# SparkFun_Dev_ESP32_C3_MINI.net
KiCad netlist of a schematic drawn in EAGLE
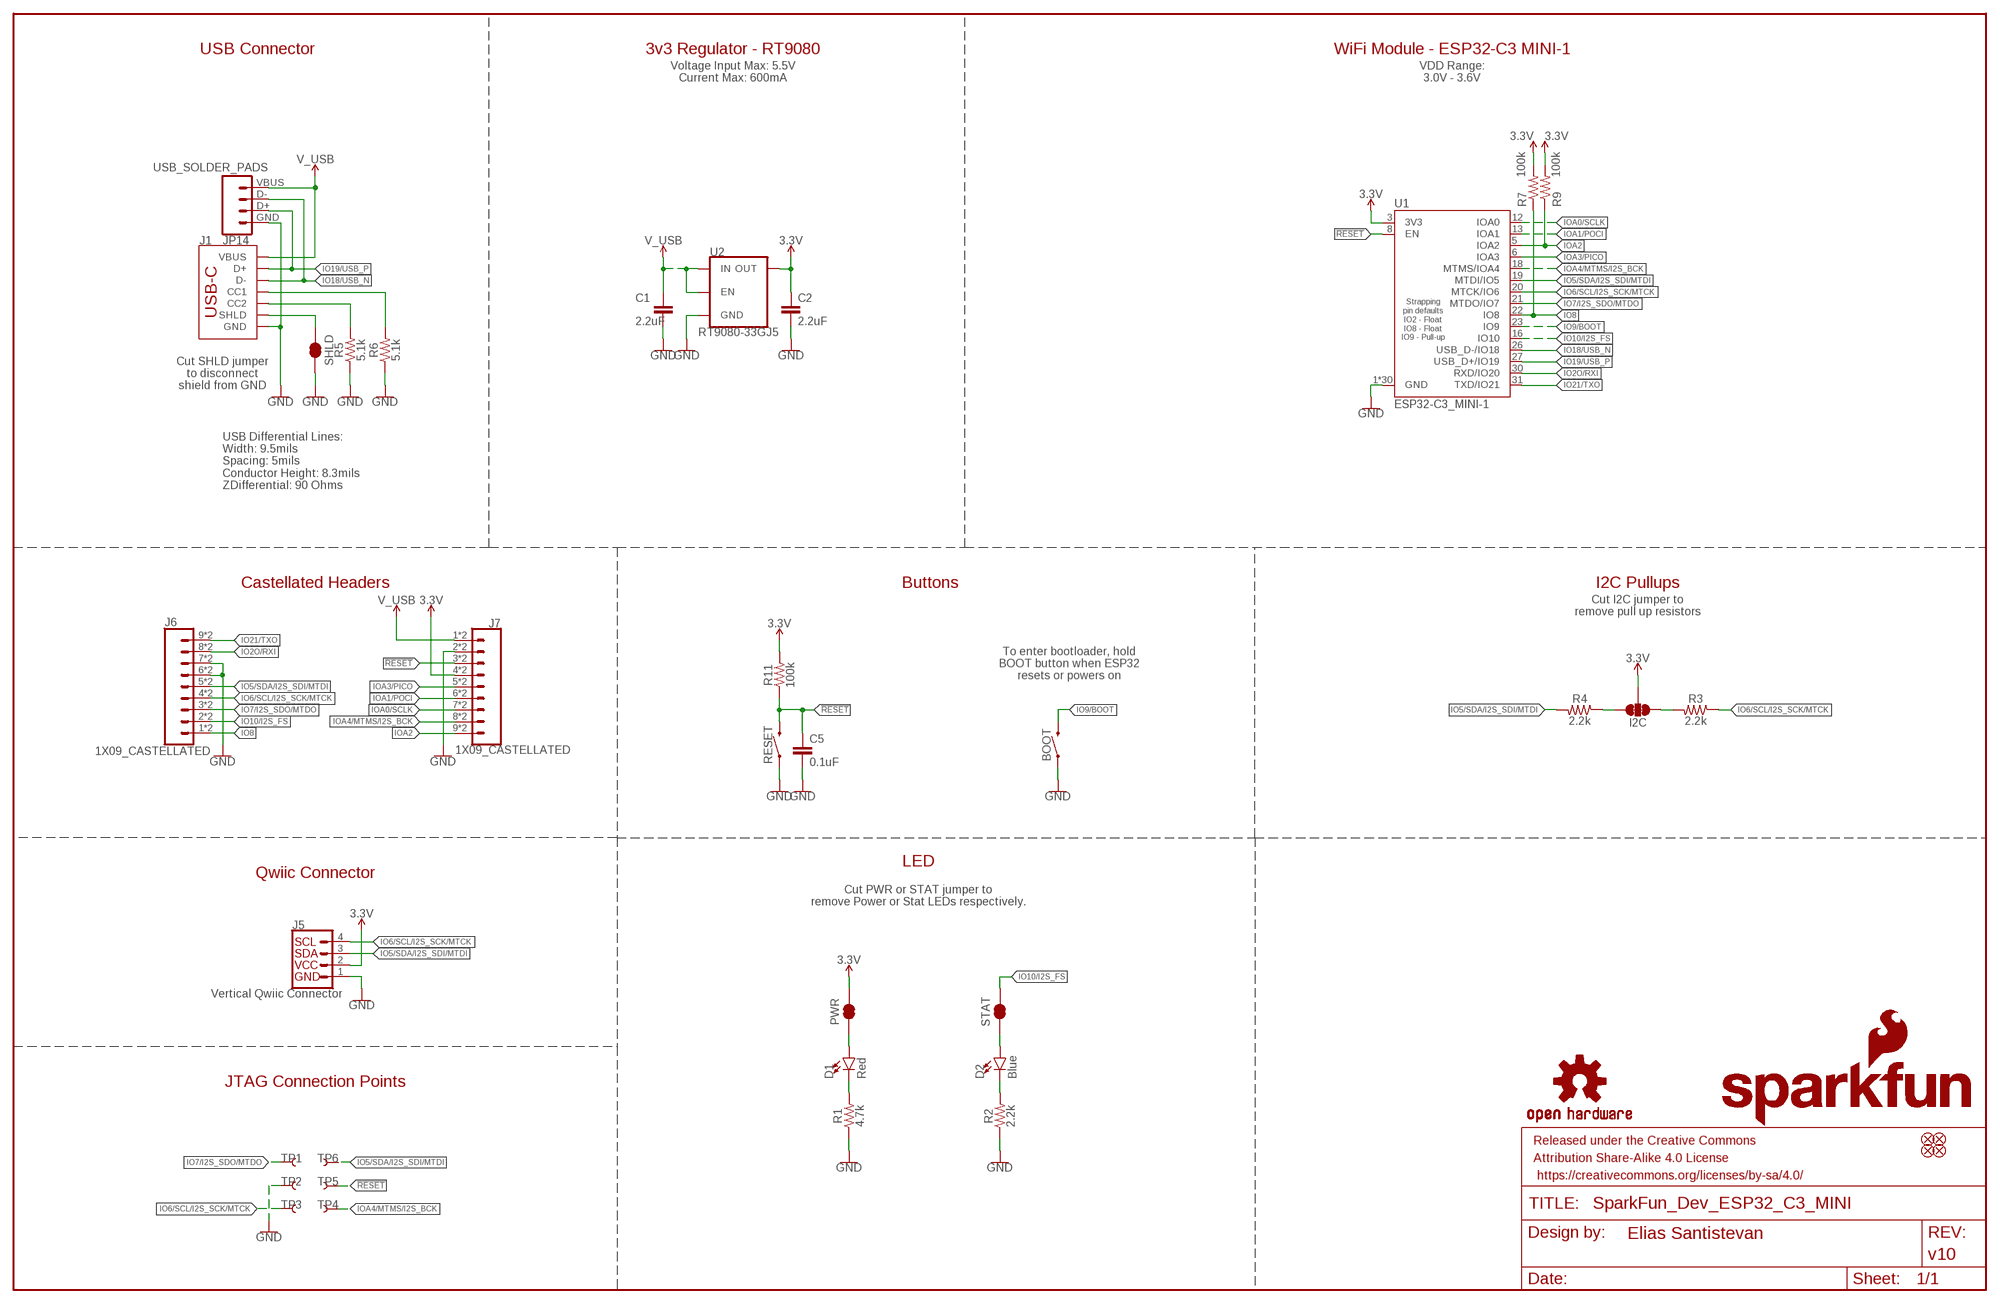
[diagram p0: schematic, sheet 1]

(export (version "E")
  (design (tool "Eeschema 10.0.6"))
  (components
    (comp (ref "BOOT")
      (value "MOMENTARY-SWITCH-SPST-SMD-4.6X2.8MM")
      (footprint "eagle-import:TACTILE_SWITCH_SMD_4.6X2.8MM")
      (libsource (lib "eagle-import") (part "MOMENTARY-SWITCH-SPST-SMD-4.6X2.8MM"))
    )
    (comp (ref "C1")
      (value "2.2uF")
      (footprint "eagle-import:0402-TIGHT")
      (libsource (lib "eagle-import") (part "2.2UF-0402_TIGHT-10V-10%-X5R"))
    )
    (comp (ref "C2")
      (value "2.2uF")
      (footprint "eagle-import:0402-TIGHT")
      (libsource (lib "eagle-import") (part "2.2UF-0402_TIGHT-10V-10%-X5R"))
    )
    (comp (ref "C5")
      (value "0.1uF")
      (footprint "eagle-import:0402-TIGHT")
      (libsource (lib "eagle-import") (part "0.1UF-0402T-6.3V-10%-X7R"))
    )
    (comp (ref "D1")
      (value "Red")
      (footprint "eagle-import:LED-0603")
      (libsource (lib "eagle-import") (part "LED-RED_0603-KB"))
    )
    (comp (ref "D2")
      (value "Blue")
      (footprint "eagle-import:LED-0603")
      (libsource (lib "eagle-import") (part "LED-BLUE0603"))
    )
    (comp (ref "FD1")
      (value "FIDUCIALUFIDUCIAL")
      (footprint "eagle-import:FIDUCIAL-MICRO")
      (libsource (lib "eagle-import") (part "FIDUCIALUFIDUCIAL"))
    )
    (comp (ref "FD2")
      (value "FIDUCIALUFIDUCIAL")
      (footprint "eagle-import:FIDUCIAL-MICRO")
      (libsource (lib "eagle-import") (part "FIDUCIALUFIDUCIAL"))
    )
    (comp (ref "FD3")
      (value "FIDUCIALUFIDUCIAL")
      (footprint "eagle-import:FIDUCIAL-MICRO")
      (libsource (lib "eagle-import") (part "FIDUCIALUFIDUCIAL"))
    )
    (comp (ref "FD4")
      (value "FIDUCIALUFIDUCIAL")
      (footprint "eagle-import:FIDUCIAL-MICRO")
      (libsource (lib "eagle-import") (part "FIDUCIALUFIDUCIAL"))
    )
    (comp (ref "FRAME2")
      (value "FRAME-LEDGER")
      (footprint "eagle-import:CREATIVE_COMMONS")
      (fields (field (name "DESIGNER") "Elias Santistevan") (field (name "REV") "v10"))
      (libsource (lib "eagle-import") (part "FRAME-LEDGER"))
    )
    (comp (ref "I2C")
      (value "JUMPER-SMT_3_2-NC_TRACE_SILK")
      (footprint "eagle-import:SMT-JUMPER_3_2-NC_TRACE_SILK")
      (libsource (lib "eagle-import") (part "JUMPER-SMT_3_2-NC_TRACE_SILK"))
    )
    (comp (ref "J1")
      (value "USB Female Type C Connector")
      (footprint "eagle-import:USB-C-16P_4LAYER-PADS")
      (libsource (lib "eagle-import") (part "USB_C_4-LAYER_PADS"))
    )
    (comp (ref "J5")
      (value "Vertical Qwiic Connector")
      (footprint "eagle-import:JST04_1MM_VERT")
      (libsource (lib "eagle-import") (part "QWIIC_CONNECTOR"))
    )
    (comp (ref "J6")
      (value "1X09_CASTELLATED")
      (footprint "eagle-import:1X09_CASTELLATED")
      (libsource (lib "eagle-import") (part "1X09_CASTELLATED"))
    )
    (comp (ref "J7")
      (value "1X09_CASTELLATED")
      (footprint "eagle-import:1X09_CASTELLATED")
      (libsource (lib "eagle-import") (part "1X09_CASTELLATED"))
    )
    (comp (ref "JP14")
      (value "USB_SOLDER_PADS")
      (footprint "eagle-import:USB-SOLDER-PADS")
      (libsource (lib "eagle-import") (part "USB_SOLDER_PADS"))
    )
    (comp (ref "LOGO1")
      (value "SFE_LOGO_NAME_FLAMEBLANK")
      (footprint "eagle-import:BLANK")
      (libsource (lib "eagle-import") (part "SFE_LOGO_NAME_FLAMEBLANK"))
    )
    (comp (ref "LOGO3")
      (value "OSHW-LOGOS")
      (footprint "eagle-import:OSHW-LOGO-S")
      (libsource (lib "eagle-import") (part "OSHW-LOGOS"))
    )
    (comp (ref "PWR")
      (value "JUMPER-SMT_2_NC_TRACE_SILK")
      (footprint "eagle-import:SMT-JUMPER_2_NC_TRACE_SILK")
      (libsource (lib "eagle-import") (part "JUMPER-SMT_2_NC_TRACE_SILK"))
    )
    (comp (ref "R1")
      (value "4.7k")
      (footprint "eagle-import:0402-TIGHT")
      (libsource (lib "eagle-import") (part "4.7KOHM-0402T-1/16W-1%"))
    )
    (comp (ref "R2")
      (value "2.2k")
      (footprint "eagle-import:0402-TIGHT")
      (libsource (lib "eagle-import") (part "2.2KOHM-0402T-1/16W-1%"))
    )
    (comp (ref "R3")
      (value "2.2k")
      (footprint "eagle-import:0402-TIGHT")
      (libsource (lib "eagle-import") (part "2.2KOHM-0402T-1/16W-1%"))
    )
    (comp (ref "R4")
      (value "2.2k")
      (footprint "eagle-import:0402-TIGHT")
      (libsource (lib "eagle-import") (part "2.2KOHM-0402T-1/16W-1%"))
    )
    (comp (ref "R5")
      (value "5.1k")
      (footprint "eagle-import:0402-TIGHT")
      (libsource (lib "eagle-import") (part "5.1KOHM-0402T-1/16W-1%"))
    )
    (comp (ref "R6")
      (value "5.1k")
      (footprint "eagle-import:0402-TIGHT")
      (libsource (lib "eagle-import") (part "5.1KOHM-0402T-1/16W-1%"))
    )
    (comp (ref "R7")
      (value "100k")
      (footprint "eagle-import:0402-TIGHT")
      (libsource (lib "eagle-import") (part "100KOHM-0402T-1/16W-1%"))
    )
    (comp (ref "R9")
      (value "100k")
      (footprint "eagle-import:0402-TIGHT")
      (libsource (lib "eagle-import") (part "100KOHM-0402T-1/16W-1%"))
    )
    (comp (ref "R11")
      (value "100k")
      (footprint "eagle-import:0402-TIGHT")
      (libsource (lib "eagle-import") (part "100KOHM-0402T-1/16W-1%"))
    )
    (comp (ref "RESET")
      (value "MOMENTARY-SWITCH-SPST-SMD-4.6X2.8MM")
      (footprint "eagle-import:TACTILE_SWITCH_SMD_4.6X2.8MM")
      (libsource (lib "eagle-import") (part "MOMENTARY-SWITCH-SPST-SMD-4.6X2.8MM"))
    )
    (comp (ref "SHLD")
      (value "JUMPER-SMT_2_NC_TRACE_SILK")
      (footprint "eagle-import:SMT-JUMPER_2_NC_TRACE_SILK")
      (libsource (lib "eagle-import") (part "JUMPER-SMT_2_NC_TRACE_SILK"))
    )
    (comp (ref "STAT")
      (value "JUMPER-SMT_2_NC_TRACE_SILK")
      (footprint "eagle-import:SMT-JUMPER_2_NC_TRACE_SILK")
      (libsource (lib "eagle-import") (part "JUMPER-SMT_2_NC_TRACE_SILK"))
    )
    (comp (ref "TP1")
      (value "TEST-POINT3X5")
      (footprint "eagle-import:PAD.03X.05")
      (libsource (lib "eagle-import") (part "TEST-POINT3X5"))
    )
    (comp (ref "TP2")
      (value "TEST-POINT3X5")
      (footprint "eagle-import:PAD.03X.05")
      (libsource (lib "eagle-import") (part "TEST-POINT3X5"))
    )
    (comp (ref "TP3")
      (value "TEST-POINT3X5")
      (footprint "eagle-import:PAD.03X.05")
      (libsource (lib "eagle-import") (part "TEST-POINT3X5"))
    )
    (comp (ref "TP4")
      (value "TEST-POINT3X5")
      (footprint "eagle-import:PAD.03X.05")
      (libsource (lib "eagle-import") (part "TEST-POINT3X5"))
    )
    (comp (ref "TP5")
      (value "TEST-POINT3X5")
      (footprint "eagle-import:PAD.03X.05")
      (libsource (lib "eagle-import") (part "TEST-POINT3X5"))
    )
    (comp (ref "TP6")
      (value "TEST-POINT3X5")
      (footprint "eagle-import:PAD.03X.05")
      (libsource (lib "eagle-import") (part "TEST-POINT3X5"))
    )
    (comp (ref "U1")
      (value "ESP32-C3_MINI-1")
      (footprint "eagle-import:ESP32-C3-MINI-1")
      (libsource (lib "eagle-import") (part "ESP32-C3_MINI-1"))
    )
    (comp (ref "U2")
      (value "RT9080-33GJ5")
      (footprint "eagle-import:SOT23-5")
      (libsource (lib "eagle-import") (part "V_REG_RT9080"))
    )
  )
  (nets
    (net (code "1") (name "/~{RESET}") (class "Default")
      (node (ref "C5") (pin "1") (pinfunction "1_1") (pintype "passive"))
      (node (ref "J7") (pin "3") (pinfunction "3_3") (pintype "passive"))
      (node (ref "J7") (pin "3B") (pinfunction "3_3B") (pintype "passive"))
      (node (ref "R11") (pin "1") (pinfunction "1_1") (pintype "passive"))
      (node (ref "RESET") (pin "3") (pinfunction "2_3") (pintype "passive"))
      (node (ref "RESET") (pin "4") (pinfunction "2_4") (pintype "passive"))
      (node (ref "TP5") (pin "1") (pinfunction "1_1") (pintype "bidirectional"))
      (node (ref "U1") (pin "8") (pinfunction "EN_8") (pintype "bidirectional"))
    )
    (net (code "2") (name "3.3V") (class "Default")
      (node (ref "C2") (pin "1") (pinfunction "1_1") (pintype "passive"))
      (node (ref "I2C") (pin "2") (pinfunction "2_2") (pintype "passive"))
      (node (ref "J5") (pin "2") (pinfunction "2_2") (pintype "power_in"))
      (node (ref "J7") (pin "4") (pinfunction "4_4") (pintype "passive"))
      (node (ref "J7") (pin "4B") (pinfunction "4_4B") (pintype "passive"))
      (node (ref "PWR") (pin "2") (pinfunction "2_2") (pintype "passive"))
      (node (ref "R11") (pin "2") (pinfunction "2_2") (pintype "passive"))
      (node (ref "R7") (pin "2") (pinfunction "2_2") (pintype "passive"))
      (node (ref "R9") (pin "2") (pinfunction "2_2") (pintype "passive"))
      (node (ref "U1") (pin "3") (pinfunction "3V3_3") (pintype "bidirectional"))
      (node (ref "U2") (pin "5") (pinfunction "OUT_5") (pintype "passive"))
    )
    (net (code "3") (name "GND") (class "Default")
      (node (ref "BOOT") (pin "1") (pinfunction "1_1") (pintype "passive"))
      (node (ref "BOOT") (pin "2") (pinfunction "1_2") (pintype "passive"))
      (node (ref "C1") (pin "2") (pinfunction "2_2") (pintype "passive"))
      (node (ref "C2") (pin "2") (pinfunction "2_2") (pintype "passive"))
      (node (ref "C5") (pin "2") (pinfunction "2_2") (pintype "passive"))
      (node (ref "J1") (pin "GND") (pinfunction "GND_GND") (pintype "bidirectional"))
      (node (ref "J1") (pin "GND2") (pinfunction "GND_GND2") (pintype "bidirectional"))
      (node (ref "J5") (pin "1") (pinfunction "1_1") (pintype "power_in"))
      (node (ref "J6") (pin "6") (pinfunction "6_6") (pintype "passive"))
      (node (ref "J6") (pin "6B") (pinfunction "6_6B") (pintype "passive"))
      (node (ref "J6") (pin "7") (pinfunction "7_7") (pintype "passive"))
      (node (ref "J6") (pin "7B") (pinfunction "7_7B") (pintype "passive"))
      (node (ref "J7") (pin "2") (pinfunction "2_2") (pintype "passive"))
      (node (ref "J7") (pin "2B") (pinfunction "2_2B") (pintype "passive"))
      (node (ref "JP14") (pin "GND") (pinfunction "4_GND") (pintype "passive"))
      (node (ref "R1") (pin "1") (pinfunction "1_1") (pintype "passive"))
      (node (ref "R2") (pin "1") (pinfunction "1_1") (pintype "passive"))
      (node (ref "R5") (pin "1") (pinfunction "1_1") (pintype "passive"))
      (node (ref "R6") (pin "1") (pinfunction "1_1") (pintype "passive"))
      (node (ref "RESET") (pin "1") (pinfunction "1_1") (pintype "passive"))
      (node (ref "RESET") (pin "2") (pinfunction "1_2") (pintype "passive"))
      (node (ref "SHLD") (pin "2") (pinfunction "2_2") (pintype "passive"))
      (node (ref "TP2") (pin "1") (pinfunction "1_1") (pintype "bidirectional"))
      (node (ref "U1") (pin "1") (pinfunction "GND_1") (pintype "bidirectional"))
      (node (ref "U1") (pin "11") (pinfunction "GND_11") (pintype "bidirectional"))
      (node (ref "U1") (pin "14") (pinfunction "GND_14") (pintype "bidirectional"))
      (node (ref "U1") (pin "2") (pinfunction "GND_2") (pintype "bidirectional"))
      (node (ref "U1") (pin "36") (pinfunction "GND_36") (pintype "bidirectional"))
      (node (ref "U1") (pin "37") (pinfunction "GND_37") (pintype "bidirectional"))
      (node (ref "U1") (pin "38") (pinfunction "GND_38") (pintype "bidirectional"))
      (node (ref "U1") (pin "39") (pinfunction "GND_39") (pintype "bidirectional"))
      (node (ref "U1") (pin "40") (pinfunction "GND_40") (pintype "bidirectional"))
      (node (ref "U1") (pin "41") (pinfunction "GND_41") (pintype "bidirectional"))
      (node (ref "U1") (pin "42") (pinfunction "GND_42") (pintype "bidirectional"))
      (node (ref "U1") (pin "43") (pinfunction "GND_43") (pintype "bidirectional"))
      (node (ref "U1") (pin "44") (pinfunction "GND_44") (pintype "bidirectional"))
      (node (ref "U1") (pin "45") (pinfunction "GND_45") (pintype "bidirectional"))
      (node (ref "U1") (pin "46") (pinfunction "GND_46") (pintype "bidirectional"))
      (node (ref "U1") (pin "47") (pinfunction "GND_47") (pintype "bidirectional"))
      (node (ref "U1") (pin "48") (pinfunction "GND_48") (pintype "bidirectional"))
      (node (ref "U1") (pin "49.1") (pinfunction "GND_49.1") (pintype "bidirectional"))
      (node (ref "U1") (pin "49.2") (pinfunction "GND_49.2") (pintype "bidirectional"))
      (node (ref "U1") (pin "49.3") (pinfunction "GND_49.3") (pintype "bidirectional"))
      (node (ref "U1") (pin "49.4") (pinfunction "GND_49.4") (pintype "bidirectional"))
      (node (ref "U1") (pin "49.5") (pinfunction "GND_49.5") (pintype "bidirectional"))
      (node (ref "U1") (pin "49.6") (pinfunction "GND_49.6") (pintype "bidirectional"))
      (node (ref "U1") (pin "49.7") (pinfunction "GND_49.7") (pintype "bidirectional"))
      (node (ref "U1") (pin "49.8") (pinfunction "GND_49.8") (pintype "bidirectional"))
      (node (ref "U1") (pin "49.9") (pinfunction "GND_49.9") (pintype "bidirectional"))
      (node (ref "U1") (pin "50") (pinfunction "GND_50") (pintype "bidirectional"))
      (node (ref "U1") (pin "51") (pinfunction "GND_51") (pintype "bidirectional"))
      (node (ref "U1") (pin "52") (pinfunction "GND_52") (pintype "bidirectional"))
      (node (ref "U1") (pin "53") (pinfunction "GND_53") (pintype "bidirectional"))
      (node (ref "U2") (pin "2") (pinfunction "GND_2") (pintype "input"))
    )
    (net (code "4") (name "IO2O{slash}RXI") (class "Default")
      (node (ref "J6") (pin "8") (pinfunction "8_8") (pintype "passive"))
      (node (ref "J6") (pin "8B") (pinfunction "8_8B") (pintype "passive"))
      (node (ref "U1") (pin "30") (pinfunction "RXD/IO20_30") (pintype "bidirectional"))
    )
    (net (code "5") (name "IO5{slash}SDA{slash}I2S_SDI{slash}MTDI") (class "Default")
      (node (ref "J5") (pin "3") (pinfunction "3_3") (pintype "passive"))
      (node (ref "J6") (pin "5") (pinfunction "5_5") (pintype "passive"))
      (node (ref "J6") (pin "5B") (pinfunction "5_5B") (pintype "passive"))
      (node (ref "R4") (pin "2") (pinfunction "2_2") (pintype "passive"))
      (node (ref "TP6") (pin "1") (pinfunction "1_1") (pintype "bidirectional"))
      (node (ref "U1") (pin "19") (pinfunction "MTDI/IO5_19") (pintype "bidirectional"))
    )
    (net (code "6") (name "IO6{slash}SCL{slash}I2S_SCK{slash}MTCK") (class "Default")
      (node (ref "J5") (pin "4") (pinfunction "4_4") (pintype "passive"))
      (node (ref "J6") (pin "4") (pinfunction "4_4") (pintype "passive"))
      (node (ref "J6") (pin "4B") (pinfunction "4_4B") (pintype "passive"))
      (node (ref "R3") (pin "1") (pinfunction "1_1") (pintype "passive"))
      (node (ref "TP3") (pin "1") (pinfunction "1_1") (pintype "bidirectional"))
      (node (ref "U1") (pin "20") (pinfunction "MTCK/IO6_20") (pintype "bidirectional"))
    )
    (net (code "7") (name "IO7{slash}I2S_SDO{slash}MTDO") (class "Default")
      (node (ref "J6") (pin "3") (pinfunction "3_3") (pintype "passive"))
      (node (ref "J6") (pin "3B") (pinfunction "3_3B") (pintype "passive"))
      (node (ref "TP1") (pin "1") (pinfunction "1_1") (pintype "bidirectional"))
      (node (ref "U1") (pin "21") (pinfunction "MTDO/IO7_21") (pintype "bidirectional"))
    )
    (net (code "8") (name "IO8") (class "Default")
      (node (ref "J6") (pin "1") (pinfunction "1_1") (pintype "passive"))
      (node (ref "J6") (pin "1B") (pinfunction "1_1B") (pintype "passive"))
      (node (ref "R7") (pin "1") (pinfunction "1_1") (pintype "passive"))
      (node (ref "U1") (pin "22") (pinfunction "IO8_22") (pintype "bidirectional"))
    )
    (net (code "9") (name "IO9{slash}BOOT") (class "Default")
      (node (ref "BOOT") (pin "3") (pinfunction "2_3") (pintype "passive"))
      (node (ref "BOOT") (pin "4") (pinfunction "2_4") (pintype "passive"))
      (node (ref "U1") (pin "23") (pinfunction "IO9_23") (pintype "bidirectional"))
    )
    (net (code "10") (name "IO10{slash}I2S_FS") (class "Default")
      (node (ref "J6") (pin "2") (pinfunction "2_2") (pintype "passive"))
      (node (ref "J6") (pin "2B") (pinfunction "2_2B") (pintype "passive"))
      (node (ref "STAT") (pin "2") (pinfunction "2_2") (pintype "passive"))
      (node (ref "U1") (pin "16") (pinfunction "IO10_16") (pintype "bidirectional"))
    )
    (net (code "11") (name "IO18{slash}USB_N") (class "Default")
      (node (ref "J1") (pin "A7") (pinfunction "D-_A7") (pintype "bidirectional"))
      (node (ref "J1") (pin "B7") (pinfunction "D-_B7") (pintype "bidirectional"))
      (node (ref "JP14") (pin "D-") (pinfunction "2_D-") (pintype "passive"))
      (node (ref "U1") (pin "26") (pinfunction "USB_D-/IO18_26") (pintype "bidirectional"))
    )
    (net (code "12") (name "IO19{slash}USB_P") (class "Default")
      (node (ref "J1") (pin "A6") (pinfunction "D+_A6") (pintype "bidirectional"))
      (node (ref "J1") (pin "B6") (pinfunction "D+_B6") (pintype "bidirectional"))
      (node (ref "JP14") (pin "D+") (pinfunction "3_D+") (pintype "passive"))
      (node (ref "U1") (pin "27") (pinfunction "USB_D+/IO19_27") (pintype "bidirectional"))
    )
    (net (code "13") (name "IO21{slash}TXO") (class "Default")
      (node (ref "J6") (pin "9") (pinfunction "9_9") (pintype "passive"))
      (node (ref "J6") (pin "9B") (pinfunction "9_9B") (pintype "passive"))
      (node (ref "U1") (pin "31") (pinfunction "TXD/IO21_31") (pintype "bidirectional"))
    )
    (net (code "14") (name "IOA0{slash}SCLK") (class "Default")
      (node (ref "J7") (pin "7") (pinfunction "7_7") (pintype "passive"))
      (node (ref "J7") (pin "7B") (pinfunction "7_7B") (pintype "passive"))
      (node (ref "U1") (pin "12") (pinfunction "IOA0_12") (pintype "bidirectional"))
    )
    (net (code "15") (name "IOA1{slash}POCI") (class "Default")
      (node (ref "J7") (pin "6") (pinfunction "6_6") (pintype "passive"))
      (node (ref "J7") (pin "6B") (pinfunction "6_6B") (pintype "passive"))
      (node (ref "U1") (pin "13") (pinfunction "IOA1_13") (pintype "bidirectional"))
    )
    (net (code "16") (name "IOA2") (class "Default")
      (node (ref "J7") (pin "9") (pinfunction "9_9") (pintype "passive"))
      (node (ref "J7") (pin "9B") (pinfunction "9_9B") (pintype "passive"))
      (node (ref "R9") (pin "1") (pinfunction "1_1") (pintype "passive"))
      (node (ref "U1") (pin "5") (pinfunction "IOA2_5") (pintype "bidirectional"))
    )
    (net (code "17") (name "IOA3{slash}PICO") (class "Default")
      (node (ref "J7") (pin "5") (pinfunction "5_5") (pintype "passive"))
      (node (ref "J7") (pin "5B") (pinfunction "5_5B") (pintype "passive"))
      (node (ref "U1") (pin "6") (pinfunction "IOA3_6") (pintype "bidirectional"))
    )
    (net (code "18") (name "IOA4{slash}MTMS{slash}I2S_BCK") (class "Default")
      (node (ref "J7") (pin "8") (pinfunction "8_8") (pintype "passive"))
      (node (ref "J7") (pin "8B") (pinfunction "8_8B") (pintype "passive"))
      (node (ref "TP4") (pin "1") (pinfunction "1_1") (pintype "bidirectional"))
      (node (ref "U1") (pin "18") (pinfunction "MTMS/IOA4_18") (pintype "bidirectional"))
    )
    (net (code "19") (name "Net-(D1-PadA)") (class "Default")
      (node (ref "D1") (pin "A") (pinfunction "A_A") (pintype "passive"))
      (node (ref "PWR") (pin "1") (pinfunction "1_1") (pintype "passive"))
    )
    (net (code "20") (name "Net-(D1-PadC)") (class "Default")
      (node (ref "D1") (pin "C") (pinfunction "C_C") (pintype "passive"))
      (node (ref "R1") (pin "2") (pinfunction "2_2") (pintype "passive"))
    )
    (net (code "21") (name "Net-(D2-PadA)") (class "Default")
      (node (ref "D2") (pin "A") (pinfunction "A_A") (pintype "passive"))
      (node (ref "STAT") (pin "1") (pinfunction "1_1") (pintype "passive"))
    )
    (net (code "22") (name "Net-(D2-PadC)") (class "Default")
      (node (ref "D2") (pin "C") (pinfunction "C_C") (pintype "passive"))
      (node (ref "R2") (pin "2") (pinfunction "2_2") (pintype "passive"))
    )
    (net (code "23") (name "Net-(I2C-Pad1)") (class "Default")
      (node (ref "I2C") (pin "1") (pinfunction "1_1") (pintype "passive"))
      (node (ref "R4") (pin "1") (pinfunction "1_1") (pintype "passive"))
    )
    (net (code "24") (name "Net-(I2C-Pad3)") (class "Default")
      (node (ref "I2C") (pin "3") (pinfunction "3_3") (pintype "passive"))
      (node (ref "R3") (pin "2") (pinfunction "2_2") (pintype "passive"))
    )
    (net (code "25") (name "Net-(J1-CC1)") (class "Default")
      (node (ref "J1") (pin "A5") (pinfunction "CC1_A5") (pintype "bidirectional"))
      (node (ref "R6") (pin "2") (pinfunction "2_2") (pintype "passive"))
    )
    (net (code "26") (name "Net-(J1-CC2)") (class "Default")
      (node (ref "J1") (pin "B5") (pinfunction "CC2_B5") (pintype "bidirectional"))
      (node (ref "R5") (pin "2") (pinfunction "2_2") (pintype "passive"))
    )
    (net (code "27") (name "Net-(J1-SHLD-PadSHLD1)") (class "Default")
      (node (ref "J1") (pin "SHLD1") (pinfunction "SHLD_SHLD1") (pintype "bidirectional"))
      (node (ref "J1") (pin "SHLD2") (pinfunction "SHLD_SHLD2") (pintype "bidirectional"))
      (node (ref "J1") (pin "SHLD3") (pinfunction "SHLD_SHLD3") (pintype "bidirectional"))
      (node (ref "J1") (pin "SHLD4") (pinfunction "SHLD_SHLD4") (pintype "bidirectional"))
      (node (ref "SHLD") (pin "1") (pinfunction "1_1") (pintype "passive"))
    )
    (net (code "28") (name "V_USB") (class "Default")
      (node (ref "C1") (pin "1") (pinfunction "1_1") (pintype "passive"))
      (node (ref "J1") (pin "VBUS1") (pinfunction "VBUS_VBUS1") (pintype "bidirectional"))
      (node (ref "J1") (pin "VBUS2") (pinfunction "VBUS_VBUS2") (pintype "bidirectional"))
      (node (ref "J7") (pin "1") (pinfunction "1_1") (pintype "passive"))
      (node (ref "J7") (pin "1B") (pinfunction "1_1B") (pintype "passive"))
      (node (ref "JP14") (pin "VBUS") (pinfunction "1_VBUS") (pintype "passive"))
      (node (ref "U2") (pin "1") (pinfunction "IN_1") (pintype "input"))
      (node (ref "U2") (pin "3") (pinfunction "EN_3") (pintype "input"))
    )
  )
)
